# WatchDog.net
KiCad netlist of a schematic drawn in EasyEDA Pro
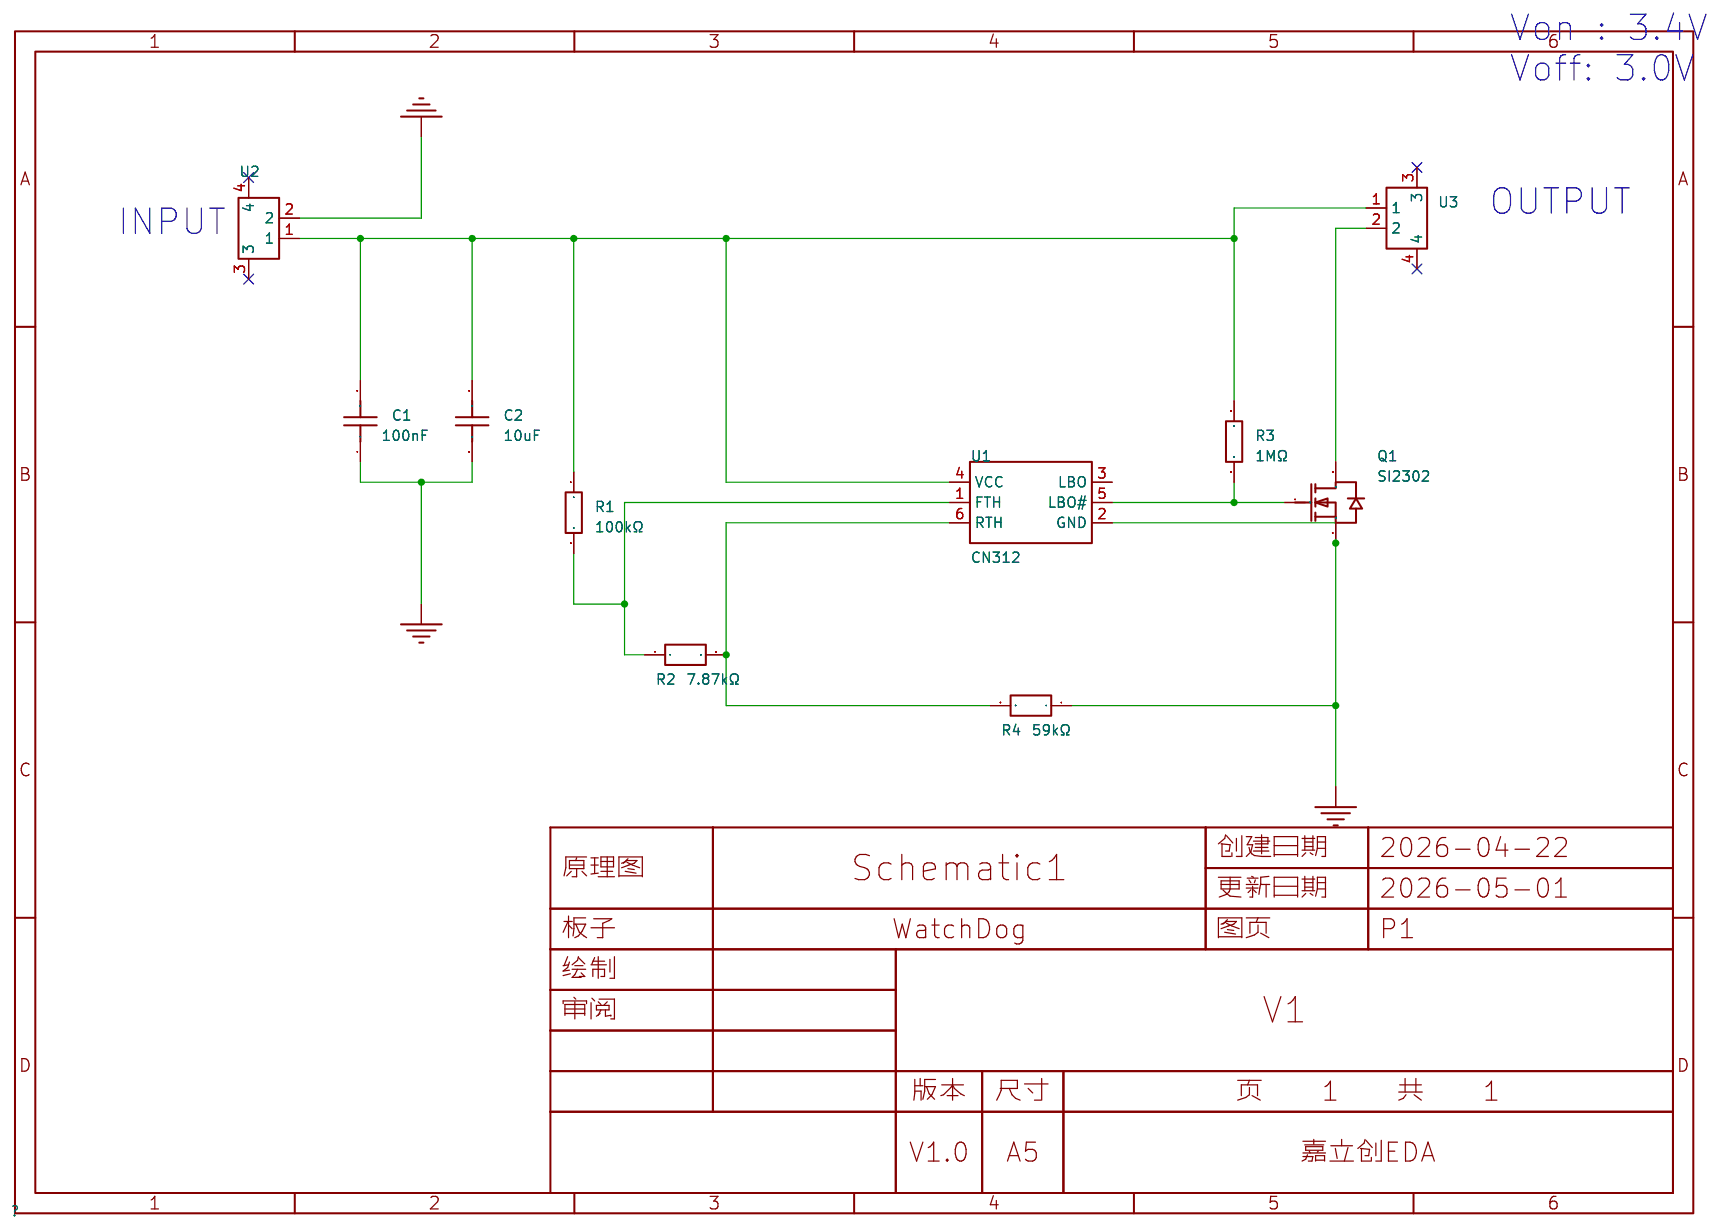
[diagram p0: schematic sheet]

(export (version "E")
  (design (tool "Eeschema 10.0.6"))
  (components
    (comp (ref "C1")
      (value "100nF")
      (footprint "easyedapro:CAP-SMD_L2.0-W1.25")
      (fields
        (field (name "Manufacturer Part") "FCC0805B104K500DT")
        (field (name "Manufacturer") "FOJAN(富捷)")
      )
      (libsource (lib "easyedapro") (part "FCC0805B104K500DT"))
    )
    (comp (ref "C2")
      (value "10uF")
      (footprint "easyedapro:C0805")
      (fields
        (field (name "Manufacturer Part") "CL21B106KOQNNNE")
        (field (name "Manufacturer") "SAMSUNG(三星)")
      )
      (libsource (lib "easyedapro") (part "CL21B106KOQNNNE"))
    )
    (comp (ref "Q1")
      (value "SI2302")
      (footprint "easyedapro:SOT-23-3_L2.9-W1.3-P1.90-LS2.4-BR")
      (fields (field (name "Manufacturer") "YONGYUTAI(永裕泰)"))
      (libsource (lib "easyedapro") (part "SI2302_C2891732"))
    )
    (comp (ref "R1")
      (value "100kΩ")
      (footprint "easyedapro:R0603")
      (fields
        (field (name "Manufacturer Part") "0603WAF1003T5E")
        (field (name "Manufacturer") "UNI-ROYAL(厚声)")
      )
      (libsource (lib "easyedapro") (part "0603WAF1003T5E"))
    )
    (comp (ref "R2")
      (value "7.87kΩ")
      (footprint "easyedapro:R0603")
      (fields (field (name "Manufacturer Part") "FRC0603F7871TS") (field (name "Manufacturer") "FOJAN(富捷)"))
      (libsource (lib "easyedapro") (part "FRC0603F7871TS"))
    )
    (comp (ref "R3")
      (value "1MΩ")
      (footprint "easyedapro:R0805")
      (fields
        (field (name "Manufacturer Part") "0805W8F1004T5E")
        (field (name "Manufacturer") "UNI-ROYAL(厚声)")
      )
      (libsource (lib "easyedapro") (part "0805W8F1004T5E"))
    )
    (comp (ref "R4")
      (value "59kΩ")
      (footprint "easyedapro:R0603")
      (fields (field (name "Manufacturer Part") "FRC0603F5902TS") (field (name "Manufacturer") "FOJAN(富捷)"))
      (libsource (lib "easyedapro") (part "FRC0603F5902TS"))
    )
    (comp (ref "U1")
      (value "CN312")
      (footprint "easyedapro:SOT-23-6_L2.9-W1.6-P0.95-LS2.8-BL")
      (fields (field (name "Manufacturer") "CONSONANCE(上海如韵)"))
      (libsource (lib "easyedapro") (part "CN312"))
    )
    (comp (ref "U2")
      (value "532610271")
      (footprint "easyedapro:CONN-SMD_532610271")
      (fields (field (name "Manufacturer") "MOLEX"))
      (libsource (lib "easyedapro") (part "532610271_C177225"))
    )
    (comp (ref "U3")
      (value "532610271")
      (footprint "easyedapro:CONN-SMD_532610271")
      (fields (field (name "Manufacturer") "MOLEX"))
      (libsource (lib "easyedapro") (part "532610271_C177225"))
    )
  )
  (nets
    (net (code "1") (name "GND") (class "Default")
      (node (ref "C1") (pin "1") (pinfunction "1_1") (pintype "unspecified"))
      (node (ref "C2") (pin "2") (pinfunction "2_2") (pintype "unspecified"))
      (node (ref "Q1") (pin "2") (pinfunction "S_2") (pintype "unspecified"))
      (node (ref "R4") (pin "1") (pinfunction "1_1") (pintype "unspecified"))
      (node (ref "U1") (pin "2") (pinfunction "GND_2") (pintype "unspecified"))
      (node (ref "U2") (pin "2") (pinfunction "2_2") (pintype "unspecified"))
    )
    (net (code "2") (name "Net-(Q1-D)") (class "Default")
      (node (ref "Q1") (pin "3") (pinfunction "D_3") (pintype "unspecified"))
      (node (ref "U3") (pin "2") (pinfunction "2_2") (pintype "unspecified"))
    )
    (net (code "3") (name "Net-(Q1-G)") (class "Default")
      (node (ref "Q1") (pin "1") (pinfunction "G_1") (pintype "unspecified"))
      (node (ref "R3") (pin "1") (pinfunction "1_1") (pintype "input"))
      (node (ref "U1") (pin "5") (pinfunction "LBO#_5") (pintype "unspecified"))
    )
    (net (code "4") (name "Net-(U1-FTH)") (class "Default")
      (node (ref "R1") (pin "2") (pinfunction "2_2") (pintype "input"))
      (node (ref "R2") (pin "1") (pinfunction "1_1") (pintype "unspecified"))
      (node (ref "U1") (pin "1") (pinfunction "FTH_1") (pintype "unspecified"))
    )
    (net (code "5") (name "Net-(U1-RTH)") (class "Default")
      (node (ref "R2") (pin "2") (pinfunction "2_2") (pintype "unspecified"))
      (node (ref "R4") (pin "2") (pinfunction "2_2") (pintype "unspecified"))
      (node (ref "U1") (pin "6") (pinfunction "RTH_6") (pintype "unspecified"))
    )
    (net (code "6") (name "Net-(U1-VCC)") (class "Default")
      (node (ref "C1") (pin "2") (pinfunction "2_2") (pintype "unspecified"))
      (node (ref "C2") (pin "1") (pinfunction "1_1") (pintype "unspecified"))
      (node (ref "R1") (pin "1") (pinfunction "1_1") (pintype "input"))
      (node (ref "R3") (pin "2") (pinfunction "2_2") (pintype "input"))
      (node (ref "U1") (pin "4") (pinfunction "VCC_4") (pintype "unspecified"))
      (node (ref "U2") (pin "1") (pinfunction "1_1") (pintype "unspecified"))
      (node (ref "U3") (pin "1") (pinfunction "1_1") (pintype "unspecified"))
    )
    (net (code "7") (name "unconnected-(U1-LBO-Pad3)") (class "Default")
      (node (ref "U1") (pin "3") (pinfunction "LBO_3") (pintype "unspecified"))
    )
    (net (code "8") (name "unconnected-(U2-Pad3)") (class "Default")
      (node (ref "U2") (pin "3") (pinfunction "3_3") (pintype "unspecified+no_connect"))
    )
    (net (code "9") (name "unconnected-(U2-Pad4)") (class "Default")
      (node (ref "U2") (pin "4") (pinfunction "4_4") (pintype "unspecified+no_connect"))
    )
    (net (code "10") (name "unconnected-(U3-Pad3)") (class "Default")
      (node (ref "U3") (pin "3") (pinfunction "3_3") (pintype "unspecified+no_connect"))
    )
    (net (code "11") (name "unconnected-(U3-Pad4)") (class "Default")
      (node (ref "U3") (pin "4") (pinfunction "4_4") (pintype "unspecified+no_connect"))
    )
  )
)
